# humidor_controller_v33.net
KiCad netlist of a schematic drawn in EAGLE
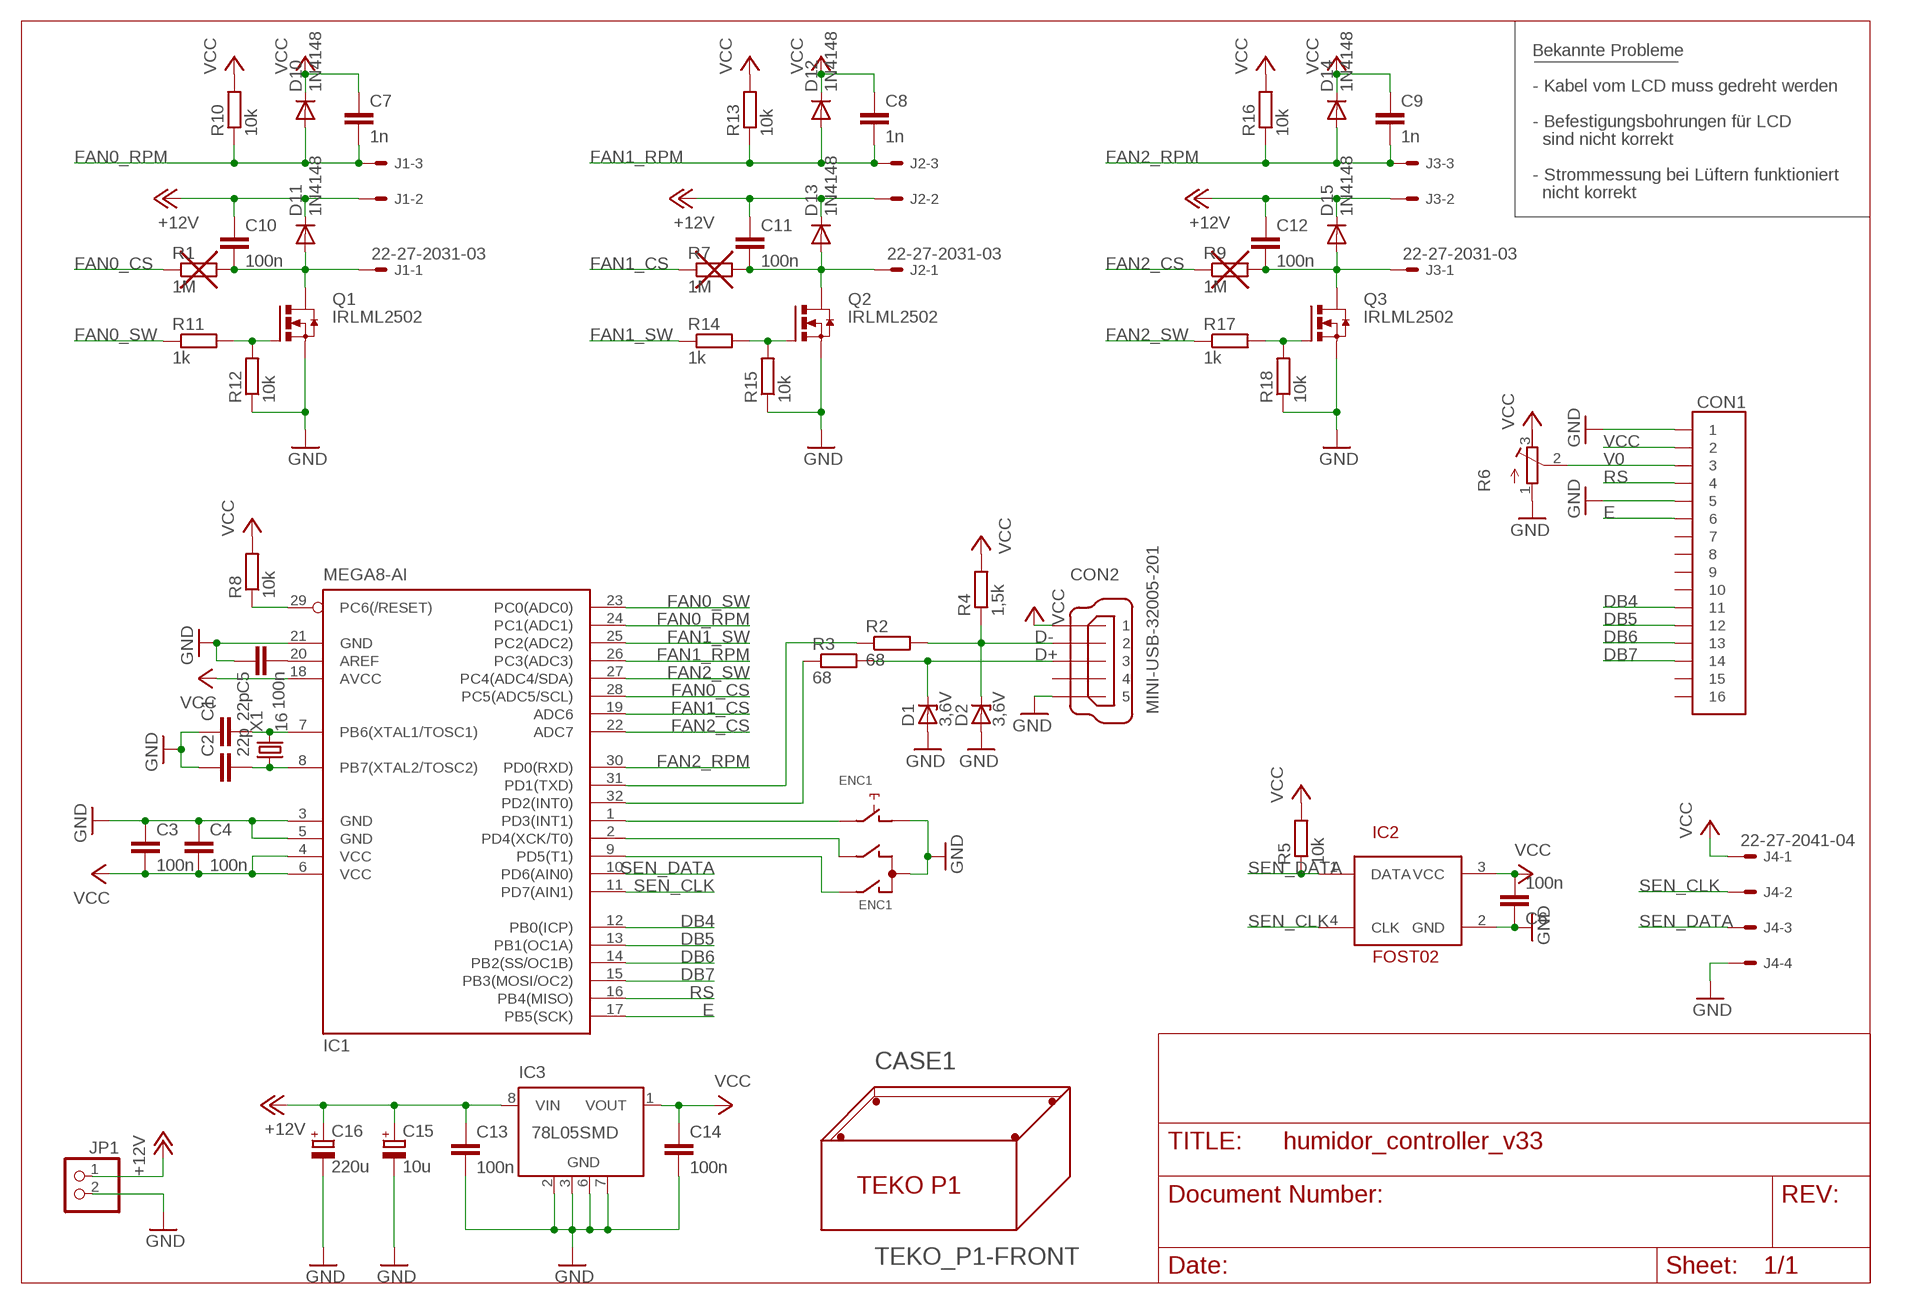
[diagram p0: schematic, sheet 1]

(export (version "E")
  (design (tool "Eeschema 10.0.6"))
  (components
    (comp (ref "C1")
      (value "22p")
      (footprint "eagle-import:C0805")
      (libsource (lib "eagle-import") (part "C-EUC0805"))
    )
    (comp (ref "C2")
      (value "22p")
      (footprint "eagle-import:C0805")
      (libsource (lib "eagle-import") (part "C-EUC0805"))
    )
    (comp (ref "C3")
      (value "100n")
      (footprint "eagle-import:C0805")
      (libsource (lib "eagle-import") (part "resistor_C-EUC0805"))
    )
    (comp (ref "C4")
      (value "100n")
      (footprint "eagle-import:C0805")
      (libsource (lib "eagle-import") (part "resistor_C-EUC0805"))
    )
    (comp (ref "C5")
      (value "100n")
      (footprint "eagle-import:C0805")
      (libsource (lib "eagle-import") (part "resistor_C-EUC0805"))
    )
    (comp (ref "C6")
      (value "100n")
      (footprint "eagle-import:C0805")
      (libsource (lib "eagle-import") (part "resistor_C-EUC0805"))
    )
    (comp (ref "C7")
      (value "1n")
      (footprint "eagle-import:C0805")
      (libsource (lib "eagle-import") (part "resistor_C-EUC0805"))
    )
    (comp (ref "C8")
      (value "1n")
      (footprint "eagle-import:C0805")
      (libsource (lib "eagle-import") (part "resistor_C-EUC0805"))
    )
    (comp (ref "C9")
      (value "1n")
      (footprint "eagle-import:C0805")
      (libsource (lib "eagle-import") (part "resistor_C-EUC0805"))
    )
    (comp (ref "C10")
      (value "100n")
      (footprint "eagle-import:C0805")
      (libsource (lib "eagle-import") (part "resistor_C-EUC0805"))
    )
    (comp (ref "C11")
      (value "100n")
      (footprint "eagle-import:C0805")
      (libsource (lib "eagle-import") (part "resistor_C-EUC0805"))
    )
    (comp (ref "C12")
      (value "100n")
      (footprint "eagle-import:C0805")
      (libsource (lib "eagle-import") (part "resistor_C-EUC0805"))
    )
    (comp (ref "C13")
      (value "100n")
      (footprint "eagle-import:C0805")
      (libsource (lib "eagle-import") (part "C-EUC0805"))
    )
    (comp (ref "C14")
      (value "100n")
      (footprint "eagle-import:C0805")
      (libsource (lib "eagle-import") (part "C-EUC0805"))
    )
    (comp (ref "C15")
      (value "10u")
      (footprint "eagle-import:PANASONIC_D")
      (libsource (lib "eagle-import") (part "CPOL-EUD"))
    )
    (comp (ref "C16")
      (value "220u")
      (footprint "eagle-import:PANASONIC_G")
      (libsource (lib "eagle-import") (part "CPOL-EUG"))
    )
    (comp (ref "CASE1")
      (value "TEKO_P1-FRONT")
      (footprint "eagle-import:TEKO_P1_FRONT")
      (libsource (lib "eagle-import") (part "TEKO_P1-FRONT"))
    )
    (comp (ref "CON1")
      (value "52207-16")
      (footprint "eagle-import:52207-16")
      (libsource (lib "eagle-import") (part "52207-16"))
    )
    (comp (ref "CON2")
      (value "MINI-USB-32005-201")
      (footprint "eagle-import:32005-201")
      (libsource (lib "eagle-import") (part "MINI-USB-32005-201"))
    )
    (comp (ref "D1")
      (value "3,6V")
      (footprint "eagle-import:SOD80C")
      (libsource (lib "eagle-import") (part "ZENER-DIODESOD80C"))
    )
    (comp (ref "D2")
      (value "3,6V")
      (footprint "eagle-import:SOD80C")
      (libsource (lib "eagle-import") (part "ZENER-DIODESOD80C"))
    )
    (comp (ref "D10")
      (value "1N4148")
      (footprint "eagle-import:SOD323-R")
      (libsource (lib "eagle-import") (part "DIODE-SOD323-R"))
    )
    (comp (ref "D11")
      (value "1N4148")
      (footprint "eagle-import:SOD323-R")
      (libsource (lib "eagle-import") (part "DIODE-SOD323-R"))
    )
    (comp (ref "D12")
      (value "1N4148")
      (footprint "eagle-import:SOD323-R")
      (libsource (lib "eagle-import") (part "DIODE-SOD323-R"))
    )
    (comp (ref "D13")
      (value "1N4148")
      (footprint "eagle-import:SOD323-R")
      (libsource (lib "eagle-import") (part "DIODE-SOD323-R"))
    )
    (comp (ref "D14")
      (value "1N4148")
      (footprint "eagle-import:SOD323-R")
      (libsource (lib "eagle-import") (part "DIODE-SOD323-R"))
    )
    (comp (ref "D15")
      (value "1N4148")
      (footprint "eagle-import:SOD323-R")
      (libsource (lib "eagle-import") (part "DIODE-SOD323-R"))
    )
    (comp (ref "ENC1")
      (value "NOBLE_RE0124")
      (footprint "eagle-import:RE0124")
      (libsource (lib "eagle-import") (part "NOBLE_RE0124"))
    )
    (comp (ref "IC1")
      (value "MEGA8-AI")
      (footprint "eagle-import:TQFP32-08")
      (libsource (lib "eagle-import") (part "MEGA8-AI"))
    )
    (comp (ref "IC2")
      (value "FOST02")
      (footprint "eagle-import:FOST02")
      (libsource (lib "eagle-import") (part "FOST02"))
    )
    (comp (ref "IC3")
      (value "78L05SMD")
      (footprint "eagle-import:SO08")
      (libsource (lib "eagle-import") (part "78LSMD05"))
    )
    (comp (ref "J1")
      (value "22-27-2031-03")
      (footprint "eagle-import:6410-03")
      (libsource (lib "eagle-import") (part "22-?-0327-2031"))
    )
    (comp (ref "J2")
      (value "22-27-2031-03")
      (footprint "eagle-import:6410-03")
      (libsource (lib "eagle-import") (part "22-?-0327-2031"))
    )
    (comp (ref "J3")
      (value "22-27-2031-03")
      (footprint "eagle-import:6410-03")
      (libsource (lib "eagle-import") (part "22-?-0327-2031"))
    )
    (comp (ref "J4")
      (value "22-27-2041-04")
      (footprint "eagle-import:6410-04")
      (libsource (lib "eagle-import") (part "22-?-0427-2041"))
    )
    (comp (ref "JP1")
      (value "PINHD-1X2")
      (footprint "eagle-import:1X02")
      (libsource (lib "eagle-import") (part "PINHD-1X2"))
    )
    (comp (ref "Q1")
      (value "IRLML2502")
      (footprint "eagle-import:SOT23")
      (libsource (lib "eagle-import") (part "N-HEXFET_?-SOT23IRLML2502"))
    )
    (comp (ref "Q2")
      (value "IRLML2502")
      (footprint "eagle-import:SOT23")
      (libsource (lib "eagle-import") (part "N-HEXFET_?-SOT23IRLML2502"))
    )
    (comp (ref "Q3")
      (value "IRLML2502")
      (footprint "eagle-import:SOT23")
      (libsource (lib "eagle-import") (part "N-HEXFET_?-SOT23IRLML2502"))
    )
    (comp (ref "R1")
      (value "1M")
      (footprint "eagle-import:R0805")
      (libsource (lib "eagle-import") (part "R-EU_R0805"))
    )
    (comp (ref "R2")
      (value "68")
      (footprint "eagle-import:R0805")
      (libsource (lib "eagle-import") (part "R-EU_R0805"))
    )
    (comp (ref "R3")
      (value "68")
      (footprint "eagle-import:R0805")
      (libsource (lib "eagle-import") (part "R-EU_R0805"))
    )
    (comp (ref "R4")
      (value "1,5k")
      (footprint "eagle-import:R0805")
      (libsource (lib "eagle-import") (part "R-EU_R0805"))
    )
    (comp (ref "R5")
      (value "10k")
      (footprint "eagle-import:R0805")
      (libsource (lib "eagle-import") (part "R-EU_R0805"))
    )
    (comp (ref "R6")
      (value "R-TRIMM4G/J")
      (footprint "eagle-import:RTRIM4G_J")
      (libsource (lib "eagle-import") (part "R-TRIMM4G/J"))
    )
    (comp (ref "R7")
      (value "1M")
      (footprint "eagle-import:R0805")
      (libsource (lib "eagle-import") (part "R-EU_R0805"))
    )
    (comp (ref "R8")
      (value "10k")
      (footprint "eagle-import:R0805")
      (libsource (lib "eagle-import") (part "R-EU_R0805"))
    )
    (comp (ref "R9")
      (value "1M")
      (footprint "eagle-import:R0805")
      (libsource (lib "eagle-import") (part "R-EU_R0805"))
    )
    (comp (ref "R10")
      (value "10k")
      (footprint "eagle-import:R0805")
      (libsource (lib "eagle-import") (part "R-EU_R0805"))
    )
    (comp (ref "R11")
      (value "1k")
      (footprint "eagle-import:R0805")
      (libsource (lib "eagle-import") (part "R-EU_R0805"))
    )
    (comp (ref "R12")
      (value "10k")
      (footprint "eagle-import:R0805")
      (libsource (lib "eagle-import") (part "R-EU_R0805"))
    )
    (comp (ref "R13")
      (value "10k")
      (footprint "eagle-import:R0805")
      (libsource (lib "eagle-import") (part "R-EU_R0805"))
    )
    (comp (ref "R14")
      (value "1k")
      (footprint "eagle-import:R0805")
      (libsource (lib "eagle-import") (part "R-EU_R0805"))
    )
    (comp (ref "R15")
      (value "10k")
      (footprint "eagle-import:R0805")
      (libsource (lib "eagle-import") (part "R-EU_R0805"))
    )
    (comp (ref "R16")
      (value "10k")
      (footprint "eagle-import:R0805")
      (libsource (lib "eagle-import") (part "R-EU_R0805"))
    )
    (comp (ref "R17")
      (value "1k")
      (footprint "eagle-import:R0805")
      (libsource (lib "eagle-import") (part "R-EU_R0805"))
    )
    (comp (ref "R18")
      (value "10k")
      (footprint "eagle-import:R0805")
      (libsource (lib "eagle-import") (part "R-EU_R0805"))
    )
    (comp (ref "X1")
      (value "16")
      (footprint "eagle-import:HC49UP")
      (libsource (lib "eagle-import") (part "CRYSTALHC49UP"))
    )
  )
  (nets
    (net (code "1") (name "+12V") (class "Default")
      (node (ref "C10") (pin "1") (pinfunction "1_1") (pintype "passive"))
      (node (ref "C11") (pin "1") (pinfunction "1_1") (pintype "passive"))
      (node (ref "C12") (pin "1") (pinfunction "1_1") (pintype "passive"))
      (node (ref "C13") (pin "1") (pinfunction "1_1") (pintype "passive"))
      (node (ref "C15") (pin "+") (pinfunction "+_+") (pintype "passive"))
      (node (ref "C16") (pin "+") (pinfunction "+_+") (pintype "passive"))
      (node (ref "D11") (pin "C") (pinfunction "C_C") (pintype "passive"))
      (node (ref "D13") (pin "C") (pinfunction "C_C") (pintype "passive"))
      (node (ref "D15") (pin "C") (pinfunction "C_C") (pintype "passive"))
      (node (ref "IC3") (pin "8") (pinfunction "VIN_8") (pintype "passive"))
      (node (ref "J1") (pin "2") (pinfunction "S_2") (pintype "passive"))
      (node (ref "J2") (pin "2") (pinfunction "S_2") (pintype "passive"))
      (node (ref "J3") (pin "2") (pinfunction "S_2") (pintype "passive"))
      (node (ref "JP1") (pin "1") (pinfunction "1_1") (pintype "passive"))
    )
    (net (code "2") (name "/D+") (class "Default")
      (node (ref "CON2") (pin "3") (pinfunction "3_3") (pintype "passive"))
      (node (ref "D1") (pin "C") (pinfunction "C_C") (pintype "passive"))
      (node (ref "R3") (pin "2") (pinfunction "2_2") (pintype "passive"))
    )
    (net (code "3") (name "/D-") (class "Default")
      (node (ref "CON2") (pin "2") (pinfunction "2_2") (pintype "passive"))
      (node (ref "D2") (pin "C") (pinfunction "C_C") (pintype "passive"))
      (node (ref "R2") (pin "2") (pinfunction "2_2") (pintype "passive"))
      (node (ref "R4") (pin "1") (pinfunction "1_1") (pintype "passive"))
    )
    (net (code "4") (name "/DB4") (class "Default")
      (node (ref "CON1") (pin "11") (pinfunction "11_11") (pintype "bidirectional"))
      (node (ref "IC1") (pin "12") (pinfunction "PB0(ICP)_12") (pintype "bidirectional"))
    )
    (net (code "5") (name "/DB5") (class "Default")
      (node (ref "CON1") (pin "12") (pinfunction "12_12") (pintype "bidirectional"))
      (node (ref "IC1") (pin "13") (pinfunction "PB1(OC1A)_13") (pintype "bidirectional"))
    )
    (net (code "6") (name "/DB6") (class "Default")
      (node (ref "CON1") (pin "13") (pinfunction "13_13") (pintype "bidirectional"))
      (node (ref "IC1") (pin "14") (pinfunction "PB2(SS/OC1B)_14") (pintype "bidirectional"))
    )
    (net (code "7") (name "/DB7") (class "Default")
      (node (ref "CON1") (pin "14") (pinfunction "14_14") (pintype "bidirectional"))
      (node (ref "IC1") (pin "15") (pinfunction "PB3(MOSI/OC2)_15") (pintype "bidirectional"))
    )
    (net (code "8") (name "/E") (class "Default")
      (node (ref "CON1") (pin "6") (pinfunction "6_6") (pintype "bidirectional"))
      (node (ref "IC1") (pin "17") (pinfunction "PB5(SCK)_17") (pintype "bidirectional"))
    )
    (net (code "9") (name "/FAN0_CS") (class "Default")
      (node (ref "IC1") (pin "28") (pinfunction "PC5(ADC5/SCL)_28") (pintype "bidirectional"))
      (node (ref "R1") (pin "1") (pinfunction "1_1") (pintype "passive"))
    )
    (net (code "10") (name "/FAN0_RPM") (class "Default")
      (node (ref "C7") (pin "2") (pinfunction "2_2") (pintype "passive"))
      (node (ref "D10") (pin "A") (pinfunction "A_A") (pintype "passive"))
      (node (ref "IC1") (pin "24") (pinfunction "PC1(ADC1)_24") (pintype "bidirectional"))
      (node (ref "J1") (pin "3") (pinfunction "S_3") (pintype "passive"))
      (node (ref "R10") (pin "1") (pinfunction "1_1") (pintype "passive"))
    )
    (net (code "11") (name "/FAN0_SW") (class "Default")
      (node (ref "IC1") (pin "23") (pinfunction "PC0(ADC0)_23") (pintype "bidirectional"))
      (node (ref "R11") (pin "1") (pinfunction "1_1") (pintype "passive"))
    )
    (net (code "12") (name "/FAN1_CS") (class "Default")
      (node (ref "IC1") (pin "19") (pinfunction "ADC6_19") (pintype "bidirectional"))
      (node (ref "R7") (pin "1") (pinfunction "1_1") (pintype "passive"))
    )
    (net (code "13") (name "/FAN1_RPM") (class "Default")
      (node (ref "C8") (pin "2") (pinfunction "2_2") (pintype "passive"))
      (node (ref "D12") (pin "A") (pinfunction "A_A") (pintype "passive"))
      (node (ref "IC1") (pin "26") (pinfunction "PC3(ADC3)_26") (pintype "bidirectional"))
      (node (ref "J2") (pin "3") (pinfunction "S_3") (pintype "passive"))
      (node (ref "R13") (pin "1") (pinfunction "1_1") (pintype "passive"))
    )
    (net (code "14") (name "/FAN1_SW") (class "Default")
      (node (ref "IC1") (pin "25") (pinfunction "PC2(ADC2)_25") (pintype "bidirectional"))
      (node (ref "R14") (pin "1") (pinfunction "1_1") (pintype "passive"))
    )
    (net (code "15") (name "/FAN2_CS") (class "Default")
      (node (ref "IC1") (pin "22") (pinfunction "ADC7_22") (pintype "bidirectional"))
      (node (ref "R9") (pin "1") (pinfunction "1_1") (pintype "passive"))
    )
    (net (code "16") (name "/FAN2_RPM") (class "Default")
      (node (ref "C9") (pin "2") (pinfunction "2_2") (pintype "passive"))
      (node (ref "D14") (pin "A") (pinfunction "A_A") (pintype "passive"))
      (node (ref "IC1") (pin "30") (pinfunction "PD0(RXD)_30") (pintype "bidirectional"))
      (node (ref "J3") (pin "3") (pinfunction "S_3") (pintype "passive"))
      (node (ref "R16") (pin "1") (pinfunction "1_1") (pintype "passive"))
    )
    (net (code "17") (name "/FAN2_SW") (class "Default")
      (node (ref "IC1") (pin "27") (pinfunction "PC4(ADC4/SDA)_27") (pintype "bidirectional"))
      (node (ref "R17") (pin "1") (pinfunction "1_1") (pintype "passive"))
    )
    (net (code "18") (name "/RS") (class "Default")
      (node (ref "CON1") (pin "4") (pinfunction "4_4") (pintype "bidirectional"))
      (node (ref "IC1") (pin "16") (pinfunction "PB4(MISO)_16") (pintype "bidirectional"))
    )
    (net (code "19") (name "/SEN_CLK") (class "Default")
      (node (ref "IC1") (pin "11") (pinfunction "PD7(AIN1)_11") (pintype "bidirectional"))
      (node (ref "IC2") (pin "4") (pinfunction "CLK_4") (pintype "input"))
      (node (ref "J4") (pin "2") (pinfunction "S_2") (pintype "passive"))
    )
    (net (code "20") (name "/SEN_DATA") (class "Default")
      (node (ref "IC1") (pin "10") (pinfunction "PD6(AIN0)_10") (pintype "bidirectional"))
      (node (ref "IC2") (pin "1") (pinfunction "DATA_1") (pintype "bidirectional"))
      (node (ref "J4") (pin "3") (pinfunction "S_3") (pintype "passive"))
      (node (ref "R5") (pin "1") (pinfunction "1_1") (pintype "passive"))
    )
    (net (code "21") (name "/V0") (class "Default")
      (node (ref "CON1") (pin "3") (pinfunction "3_3") (pintype "bidirectional"))
      (node (ref "R6") (pin "2") (pinfunction "S_2") (pintype "passive"))
    )
    (net (code "22") (name "GND") (class "Default")
      (node (ref "C1") (pin "1") (pinfunction "1_1") (pintype "passive"))
      (node (ref "C13") (pin "2") (pinfunction "2_2") (pintype "passive"))
      (node (ref "C14") (pin "2") (pinfunction "2_2") (pintype "passive"))
      (node (ref "C15") (pin "-") (pinfunction "-_-") (pintype "passive"))
      (node (ref "C16") (pin "-") (pinfunction "-_-") (pintype "passive"))
      (node (ref "C2") (pin "1") (pinfunction "1_1") (pintype "passive"))
      (node (ref "C3") (pin "1") (pinfunction "1_1") (pintype "passive"))
      (node (ref "C4") (pin "1") (pinfunction "1_1") (pintype "passive"))
      (node (ref "C5") (pin "1") (pinfunction "1_1") (pintype "passive"))
      (node (ref "C6") (pin "1") (pinfunction "1_1") (pintype "passive"))
      (node (ref "CON1") (pin "1") (pinfunction "1_1") (pintype "bidirectional"))
      (node (ref "CON1") (pin "5") (pinfunction "5_5") (pintype "bidirectional"))
      (node (ref "CON2") (pin "5") (pinfunction "5_5") (pintype "passive"))
      (node (ref "D1") (pin "A") (pinfunction "A_A") (pintype "passive"))
      (node (ref "D2") (pin "A") (pinfunction "A_A") (pintype "passive"))
      (node (ref "ENC1") (pin "+") (pinfunction "1_+") (pintype "passive"))
      (node (ref "ENC1") (pin "C") (pinfunction "C_C") (pintype "passive"))
      (node (ref "IC1") (pin "21") (pinfunction "GND_21") (pintype "power_in"))
      (node (ref "IC1") (pin "3") (pinfunction "GND_3") (pintype "power_in"))
      (node (ref "IC1") (pin "5") (pinfunction "GND_5") (pintype "power_in"))
      (node (ref "IC2") (pin "2") (pinfunction "GND_2") (pintype "power_in"))
      (node (ref "IC3") (pin "2") (pinfunction "GND_2") (pintype "power_in"))
      (node (ref "IC3") (pin "3") (pinfunction "GND_3") (pintype "power_in"))
      (node (ref "IC3") (pin "6") (pinfunction "GND_6") (pintype "power_in"))
      (node (ref "IC3") (pin "7") (pinfunction "GND_7") (pintype "power_in"))
      (node (ref "J4") (pin "4") (pinfunction "S_4") (pintype "passive"))
      (node (ref "JP1") (pin "2") (pinfunction "2_2") (pintype "passive"))
      (node (ref "Q1") (pin "2") (pinfunction "S_2") (pintype "passive"))
      (node (ref "Q2") (pin "2") (pinfunction "S_2") (pintype "passive"))
      (node (ref "Q3") (pin "2") (pinfunction "S_2") (pintype "passive"))
      (node (ref "R12") (pin "1") (pinfunction "1_1") (pintype "passive"))
      (node (ref "R15") (pin "1") (pinfunction "1_1") (pintype "passive"))
      (node (ref "R18") (pin "1") (pinfunction "1_1") (pintype "passive"))
      (node (ref "R6") (pin "1") (pinfunction "E_1") (pintype "passive"))
    )
    (net (code "23") (name "Net-(ENC1B-2)") (class "Default")
      (node (ref "ENC1") (pin "-") (pinfunction "2_-") (pintype "passive"))
      (node (ref "IC1") (pin "1") (pinfunction "PD3(INT1)_1") (pintype "bidirectional"))
    )
    (net (code "24") (name "Net-(IC1-AREF)") (class "Default")
      (node (ref "C5") (pin "2") (pinfunction "2_2") (pintype "passive"))
      (node (ref "IC1") (pin "20") (pinfunction "AREF_20") (pintype "passive"))
    )
    (net (code "25") (name "Net-(IC1-PB6(XTAL1{slash}TOSC1))") (class "Default")
      (node (ref "C1") (pin "2") (pinfunction "2_2") (pintype "passive"))
      (node (ref "IC1") (pin "7") (pinfunction "PB6(XTAL1/TOSC1)_7") (pintype "bidirectional"))
      (node (ref "X1") (pin "2") (pinfunction "2_2") (pintype "passive"))
    )
    (net (code "26") (name "Net-(IC1-PB7(XTAL2{slash}TOSC2))") (class "Default")
      (node (ref "C2") (pin "2") (pinfunction "2_2") (pintype "passive"))
      (node (ref "IC1") (pin "8") (pinfunction "PB7(XTAL2/TOSC2)_8") (pintype "bidirectional"))
      (node (ref "X1") (pin "1") (pinfunction "1_1") (pintype "passive"))
    )
    (net (code "27") (name "Net-(IC1-PC6({slash}RESET))") (class "Default")
      (node (ref "IC1") (pin "29") (pinfunction "PC6(/RESET)_29") (pintype "bidirectional"))
      (node (ref "R8") (pin "1") (pinfunction "1_1") (pintype "passive"))
    )
    (net (code "28") (name "Net-(IC1-PD1(TXD))") (class "Default")
      (node (ref "IC1") (pin "31") (pinfunction "PD1(TXD)_31") (pintype "bidirectional"))
      (node (ref "R2") (pin "1") (pinfunction "1_1") (pintype "passive"))
    )
    (net (code "29") (name "Net-(IC1-PD2(INT0))") (class "Default")
      (node (ref "IC1") (pin "32") (pinfunction "PD2(INT0)_32") (pintype "bidirectional"))
      (node (ref "R3") (pin "1") (pinfunction "1_1") (pintype "passive"))
    )
    (net (code "30") (name "Net-(IC1-PD4(XCK{slash}T0))") (class "Default")
      (node (ref "ENC1") (pin "B") (pinfunction "B_B") (pintype "passive"))
      (node (ref "IC1") (pin "2") (pinfunction "PD4(XCK/T0)_2") (pintype "bidirectional"))
    )
    (net (code "31") (name "Net-(IC1-PD5(T1))") (class "Default")
      (node (ref "ENC1") (pin "A") (pinfunction "A_A") (pintype "passive"))
      (node (ref "IC1") (pin "9") (pinfunction "PD5(T1)_9") (pintype "bidirectional"))
    )
    (net (code "32") (name "Net-(J1A-S)") (class "Default")
      (node (ref "C10") (pin "2") (pinfunction "2_2") (pintype "passive"))
      (node (ref "D11") (pin "A") (pinfunction "A_A") (pintype "passive"))
      (node (ref "J1") (pin "1") (pinfunction "S_1") (pintype "passive"))
      (node (ref "Q1") (pin "3") (pinfunction "D_3") (pintype "passive"))
      (node (ref "R1") (pin "2") (pinfunction "2_2") (pintype "passive"))
    )
    (net (code "33") (name "Net-(J2A-S)") (class "Default")
      (node (ref "C11") (pin "2") (pinfunction "2_2") (pintype "passive"))
      (node (ref "D13") (pin "A") (pinfunction "A_A") (pintype "passive"))
      (node (ref "J2") (pin "1") (pinfunction "S_1") (pintype "passive"))
      (node (ref "Q2") (pin "3") (pinfunction "D_3") (pintype "passive"))
      (node (ref "R7") (pin "2") (pinfunction "2_2") (pintype "passive"))
    )
    (net (code "34") (name "Net-(J3A-S)") (class "Default")
      (node (ref "C12") (pin "2") (pinfunction "2_2") (pintype "passive"))
      (node (ref "D15") (pin "A") (pinfunction "A_A") (pintype "passive"))
      (node (ref "J3") (pin "1") (pinfunction "S_1") (pintype "passive"))
      (node (ref "Q3") (pin "3") (pinfunction "D_3") (pintype "passive"))
      (node (ref "R9") (pin "2") (pinfunction "2_2") (pintype "passive"))
    )
    (net (code "35") (name "Net-(Q1-G)") (class "Default")
      (node (ref "Q1") (pin "1") (pinfunction "G_1") (pintype "passive"))
      (node (ref "R11") (pin "2") (pinfunction "2_2") (pintype "passive"))
      (node (ref "R12") (pin "2") (pinfunction "2_2") (pintype "passive"))
    )
    (net (code "36") (name "Net-(Q2-G)") (class "Default")
      (node (ref "Q2") (pin "1") (pinfunction "G_1") (pintype "passive"))
      (node (ref "R14") (pin "2") (pinfunction "2_2") (pintype "passive"))
      (node (ref "R15") (pin "2") (pinfunction "2_2") (pintype "passive"))
    )
    (net (code "37") (name "Net-(Q3-G)") (class "Default")
      (node (ref "Q3") (pin "1") (pinfunction "G_1") (pintype "passive"))
      (node (ref "R17") (pin "2") (pinfunction "2_2") (pintype "passive"))
      (node (ref "R18") (pin "2") (pinfunction "2_2") (pintype "passive"))
    )
    (net (code "38") (name "VCC") (class "Default")
      (node (ref "C14") (pin "1") (pinfunction "1_1") (pintype "passive"))
      (node (ref "C3") (pin "2") (pinfunction "2_2") (pintype "passive"))
      (node (ref "C4") (pin "2") (pinfunction "2_2") (pintype "passive"))
      (node (ref "C6") (pin "2") (pinfunction "2_2") (pintype "passive"))
      (node (ref "C7") (pin "1") (pinfunction "1_1") (pintype "passive"))
      (node (ref "C8") (pin "1") (pinfunction "1_1") (pintype "passive"))
      (node (ref "C9") (pin "1") (pinfunction "1_1") (pintype "passive"))
      (node (ref "CON1") (pin "2") (pinfunction "2_2") (pintype "bidirectional"))
      (node (ref "CON2") (pin "1") (pinfunction "1_1") (pintype "passive"))
      (node (ref "D10") (pin "C") (pinfunction "C_C") (pintype "passive"))
      (node (ref "D12") (pin "C") (pinfunction "C_C") (pintype "passive"))
      (node (ref "D14") (pin "C") (pinfunction "C_C") (pintype "passive"))
      (node (ref "IC1") (pin "18") (pinfunction "AVCC_18") (pintype "power_in"))
      (node (ref "IC1") (pin "4") (pinfunction "VCC_4") (pintype "power_in"))
      (node (ref "IC1") (pin "6") (pinfunction "VCC_6") (pintype "power_in"))
      (node (ref "IC2") (pin "3") (pinfunction "VCC_3") (pintype "power_in"))
      (node (ref "IC3") (pin "1") (pinfunction "VOUT_1") (pintype "output"))
      (node (ref "J4") (pin "1") (pinfunction "S_1") (pintype "passive"))
      (node (ref "R10") (pin "2") (pinfunction "2_2") (pintype "passive"))
      (node (ref "R13") (pin "2") (pinfunction "2_2") (pintype "passive"))
      (node (ref "R16") (pin "2") (pinfunction "2_2") (pintype "passive"))
      (node (ref "R4") (pin "2") (pinfunction "2_2") (pintype "passive"))
      (node (ref "R5") (pin "2") (pinfunction "2_2") (pintype "passive"))
      (node (ref "R6") (pin "3") (pinfunction "A_3") (pintype "passive"))
      (node (ref "R8") (pin "2") (pinfunction "2_2") (pintype "passive"))
    )
    (net (code "39") (name "unconnected-(CON1-Pad7)") (class "Default")
      (node (ref "CON1") (pin "7") (pinfunction "7_7") (pintype "bidirectional"))
    )
    (net (code "40") (name "unconnected-(CON1-Pad8)") (class "Default")
      (node (ref "CON1") (pin "8") (pinfunction "8_8") (pintype "bidirectional"))
    )
    (net (code "41") (name "unconnected-(CON1-Pad9)") (class "Default")
      (node (ref "CON1") (pin "9") (pinfunction "9_9") (pintype "bidirectional"))
    )
    (net (code "42") (name "unconnected-(CON1-Pad10)") (class "Default")
      (node (ref "CON1") (pin "10") (pinfunction "10_10") (pintype "bidirectional"))
    )
    (net (code "43") (name "unconnected-(CON1-Pad15)") (class "Default")
      (node (ref "CON1") (pin "15") (pinfunction "15_15") (pintype "bidirectional"))
    )
    (net (code "44") (name "unconnected-(CON1-Pad16)") (class "Default")
      (node (ref "CON1") (pin "16") (pinfunction "16_16") (pintype "bidirectional"))
    )
    (net (code "45") (name "unconnected-(CON2-Pad4)") (class "Default")
      (node (ref "CON2") (pin "4") (pinfunction "4_4") (pintype "passive"))
    )
  )
)
